# SC.net
KiCad netlist of a schematic drawn in EAGLE
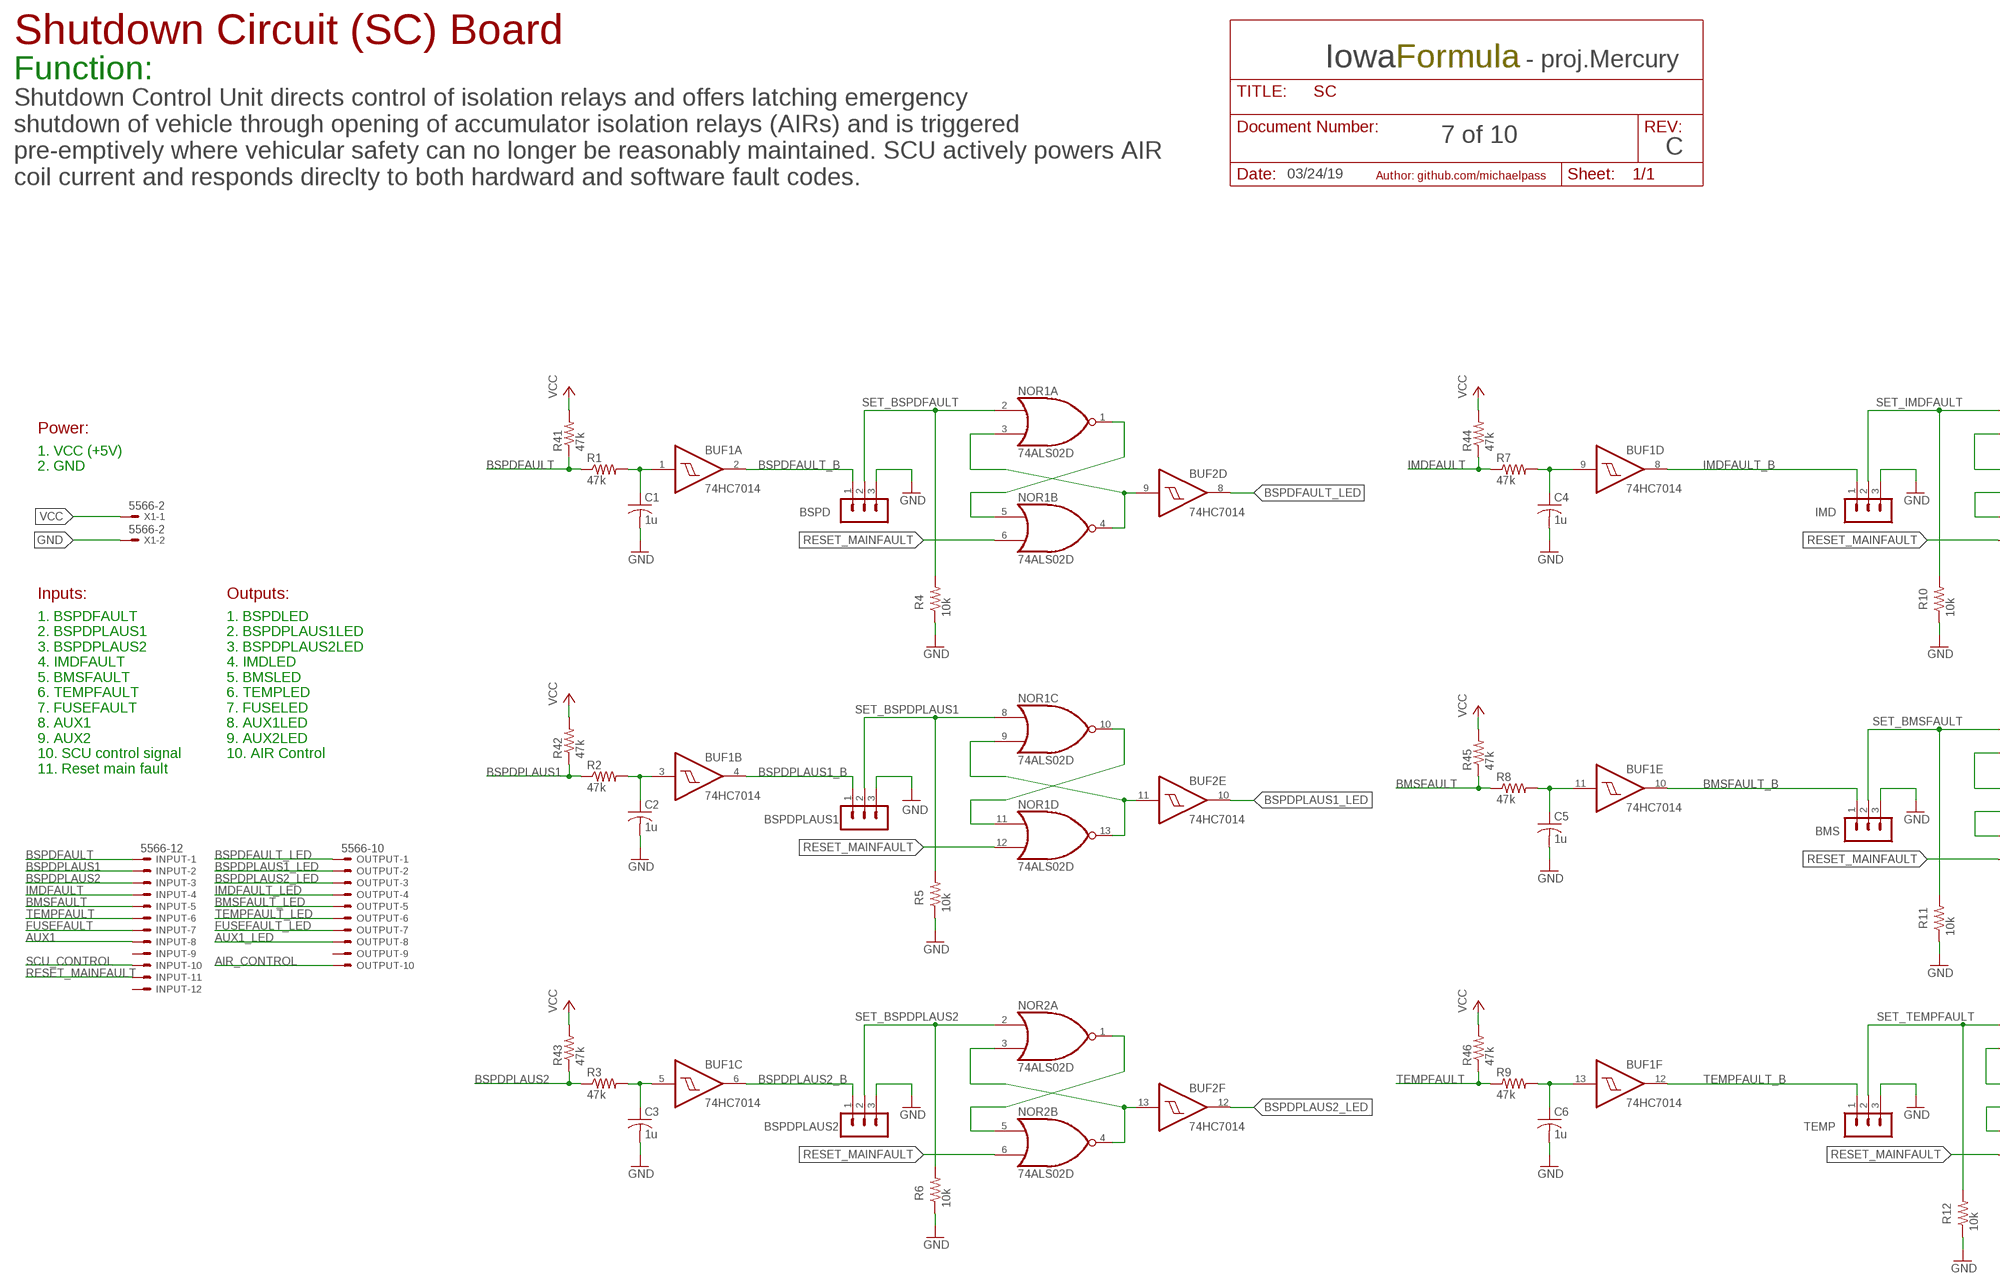
[diagram p0: schematic, sheet 1, part 1 of 3]
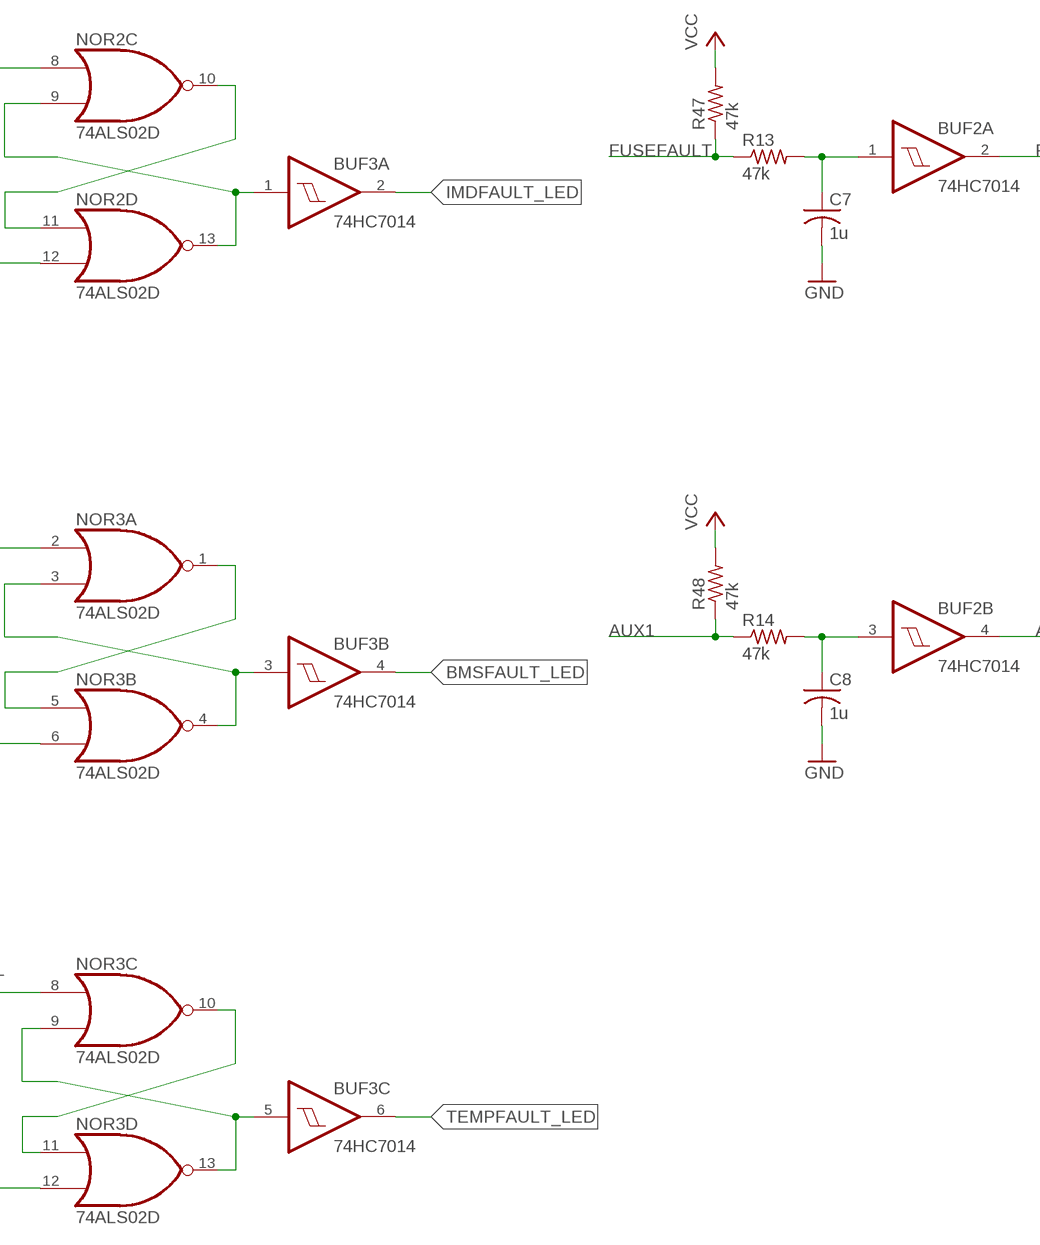
[diagram p1: schematic, sheet 1, part 2 of 3]
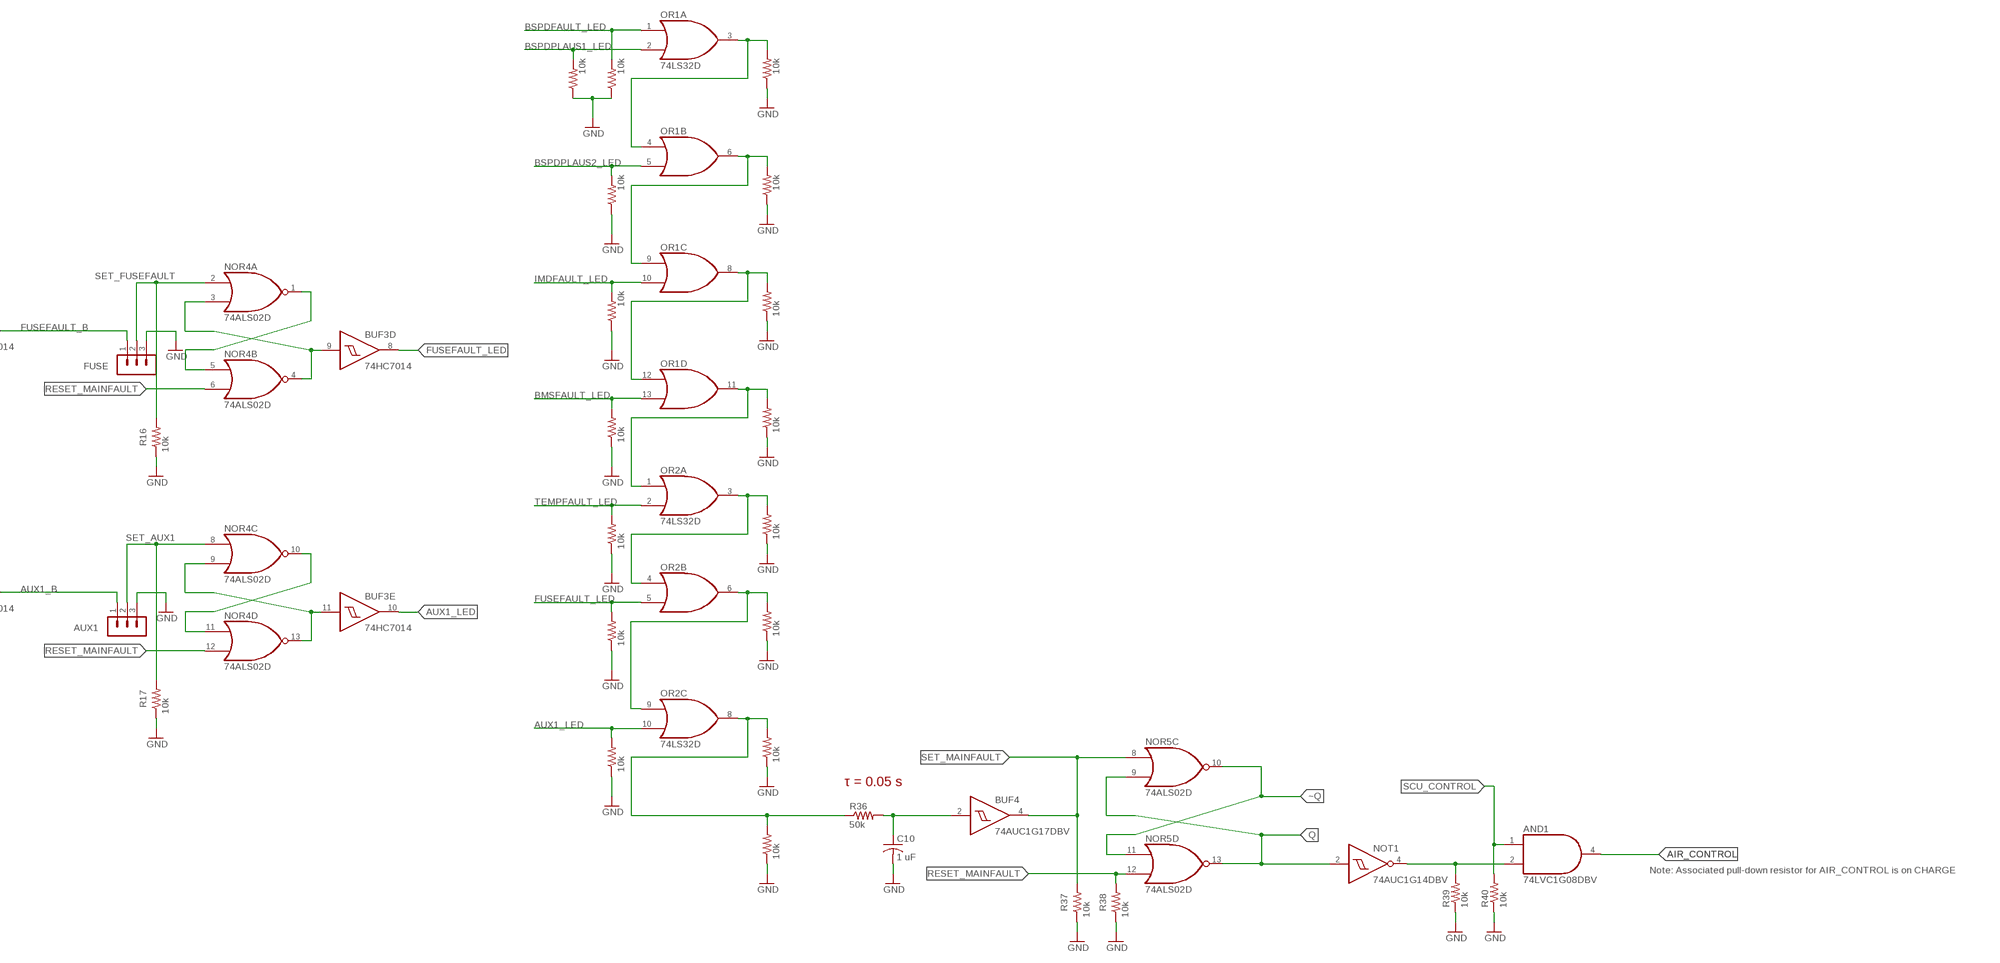
[diagram p2: schematic, sheet 1, part 3 of 3]

(export (version "E")
  (design (tool "Eeschema 10.0.6"))
  (components
    (comp (ref "AND1")
      (value "74LVC1G08DBV")
      (footprint "eagle-import:SOT23-5")
      (libsource (lib "eagle-import") (part "741G08DBVLVC"))
    )
    (comp (ref "AUX1")
      (value "MA03-1")
      (footprint "eagle-import:MA03-1")
      (libsource (lib "eagle-import") (part "MA03-1"))
    )
    (comp (ref "BMS")
      (value "MA03-1")
      (footprint "eagle-import:MA03-1")
      (libsource (lib "eagle-import") (part "MA03-1"))
    )
    (comp (ref "BSPD")
      (value "MA03-1")
      (footprint "eagle-import:MA03-1")
      (libsource (lib "eagle-import") (part "MA03-1"))
    )
    (comp (ref "BSPDPLAUS1")
      (value "MA03-1")
      (footprint "eagle-import:MA03-1")
      (libsource (lib "eagle-import") (part "MA03-1"))
    )
    (comp (ref "BSPDPLAUS2")
      (value "MA03-1")
      (footprint "eagle-import:MA03-1")
      (libsource (lib "eagle-import") (part "MA03-1"))
    )
    (comp (ref "BUF1")
      (value "74HC7014")
      (footprint "eagle-import:SO14")
      (libsource (lib "eagle-import") (part "74HC7014"))
    )
    (comp (ref "BUF2")
      (value "74HC7014")
      (footprint "eagle-import:SO14")
      (libsource (lib "eagle-import") (part "74HC7014"))
    )
    (comp (ref "BUF3")
      (value "74HC7014")
      (footprint "eagle-import:SO14")
      (libsource (lib "eagle-import") (part "74HC7014"))
    )
    (comp (ref "BUF4")
      (value "74AUC1G17DBV")
      (footprint "eagle-import:SOT23-5")
      (libsource (lib "eagle-import") (part "741G17DBVAUC"))
    )
    (comp (ref "C1")
      (value "1u")
      (footprint "eagle-import:C0805")
      (libsource (lib "eagle-import") (part "C-USC0805"))
    )
    (comp (ref "C2")
      (value "1u")
      (footprint "eagle-import:C0805")
      (libsource (lib "eagle-import") (part "C-USC0805"))
    )
    (comp (ref "C3")
      (value "1u")
      (footprint "eagle-import:C0805")
      (libsource (lib "eagle-import") (part "C-USC0805"))
    )
    (comp (ref "C4")
      (value "1u")
      (footprint "eagle-import:C0805")
      (libsource (lib "eagle-import") (part "C-USC0805"))
    )
    (comp (ref "C5")
      (value "1u")
      (footprint "eagle-import:C0805")
      (libsource (lib "eagle-import") (part "C-USC0805"))
    )
    (comp (ref "C6")
      (value "1u")
      (footprint "eagle-import:C0805")
      (libsource (lib "eagle-import") (part "C-USC0805"))
    )
    (comp (ref "C7")
      (value "1u")
      (footprint "eagle-import:C0805")
      (libsource (lib "eagle-import") (part "C-USC0805"))
    )
    (comp (ref "C8")
      (value "1u")
      (footprint "eagle-import:C0805")
      (libsource (lib "eagle-import") (part "C-USC0805"))
    )
    (comp (ref "C10")
      (value "1 uF")
      (footprint "eagle-import:C0805")
      (libsource (lib "eagle-import") (part "C-USC0805"))
    )
    (comp (ref "FUSE")
      (value "MA03-1")
      (footprint "eagle-import:MA03-1")
      (libsource (lib "eagle-import") (part "MA03-1"))
    )
    (comp (ref "IMD")
      (value "MA03-1")
      (footprint "eagle-import:MA03-1")
      (libsource (lib "eagle-import") (part "MA03-1"))
    )
    (comp (ref "INPUT")
      (value "5566-12")
      (footprint "eagle-import:5566-12")
      (fields (field (name "MF") "MOLEX"))
      (libsource (lib "eagle-import") (part "5566-12"))
    )
    (comp (ref "NOR1")
      (value "74ALS02D")
      (footprint "eagle-import:SO14")
      (libsource (lib "eagle-import") (part "7402DALS"))
    )
    (comp (ref "NOR2")
      (value "74ALS02D")
      (footprint "eagle-import:SO14")
      (libsource (lib "eagle-import") (part "7402DALS"))
    )
    (comp (ref "NOR3")
      (value "74ALS02D")
      (footprint "eagle-import:SO14")
      (libsource (lib "eagle-import") (part "7402DALS"))
    )
    (comp (ref "NOR4")
      (value "74ALS02D")
      (footprint "eagle-import:SO14")
      (libsource (lib "eagle-import") (part "7402DALS"))
    )
    (comp (ref "NOR5")
      (value "74ALS02D")
      (footprint "eagle-import:SO14")
      (libsource (lib "eagle-import") (part "7402DALS"))
    )
    (comp (ref "NOT1")
      (value "74AUC1G14DBV")
      (footprint "eagle-import:SOT23-5")
      (libsource (lib "eagle-import") (part "741G14DBVAUC"))
    )
    (comp (ref "OR1")
      (value "74LS32D")
      (footprint "eagle-import:SO14")
      (libsource (lib "eagle-import") (part "7432DLS"))
    )
    (comp (ref "OR2")
      (value "74LS32D")
      (footprint "eagle-import:SO14")
      (libsource (lib "eagle-import") (part "7432DLS"))
    )
    (comp (ref "OUTPUT")
      (value "5566-10")
      (footprint "eagle-import:5566-10")
      (fields (field (name "MF") "MOLEX"))
      (libsource (lib "eagle-import") (part "5566-10"))
    )
    (comp (ref "R1")
      (value "47k")
      (footprint "eagle-import:R0805")
      (libsource (lib "eagle-import") (part "R-US_R0805"))
    )
    (comp (ref "R2")
      (value "47k")
      (footprint "eagle-import:R0805")
      (libsource (lib "eagle-import") (part "R-US_R0805"))
    )
    (comp (ref "R3")
      (value "47k")
      (footprint "eagle-import:R0805")
      (libsource (lib "eagle-import") (part "R-US_R0805"))
    )
    (comp (ref "R4")
      (value "10k")
      (footprint "eagle-import:R0805")
      (libsource (lib "eagle-import") (part "R-US_R0805"))
    )
    (comp (ref "R5")
      (value "10k")
      (footprint "eagle-import:R0805")
      (libsource (lib "eagle-import") (part "R-US_R0805"))
    )
    (comp (ref "R6")
      (value "10k")
      (footprint "eagle-import:R0805")
      (libsource (lib "eagle-import") (part "R-US_R0805"))
    )
    (comp (ref "R7")
      (value "47k")
      (footprint "eagle-import:R0805")
      (libsource (lib "eagle-import") (part "R-US_R0805"))
    )
    (comp (ref "R8")
      (value "47k")
      (footprint "eagle-import:R0805")
      (libsource (lib "eagle-import") (part "R-US_R0805"))
    )
    (comp (ref "R9")
      (value "47k")
      (footprint "eagle-import:R0805")
      (libsource (lib "eagle-import") (part "R-US_R0805"))
    )
    (comp (ref "R10")
      (value "10k")
      (footprint "eagle-import:R0805")
      (libsource (lib "eagle-import") (part "R-US_R0805"))
    )
    (comp (ref "R11")
      (value "10k")
      (footprint "eagle-import:R0805")
      (libsource (lib "eagle-import") (part "R-US_R0805"))
    )
    (comp (ref "R12")
      (value "10k")
      (footprint "eagle-import:R0805")
      (libsource (lib "eagle-import") (part "R-US_R0805"))
    )
    (comp (ref "R13")
      (value "47k")
      (footprint "eagle-import:R0805")
      (libsource (lib "eagle-import") (part "R-US_R0805"))
    )
    (comp (ref "R14")
      (value "47k")
      (footprint "eagle-import:R0805")
      (libsource (lib "eagle-import") (part "R-US_R0805"))
    )
    (comp (ref "R16")
      (value "10k")
      (footprint "eagle-import:R0805")
      (libsource (lib "eagle-import") (part "R-US_R0805"))
    )
    (comp (ref "R17")
      (value "10k")
      (footprint "eagle-import:R0805")
      (libsource (lib "eagle-import") (part "R-US_R0805"))
    )
    (comp (ref "R19")
      (value "10k")
      (footprint "eagle-import:R0805")
      (libsource (lib "eagle-import") (part "R-US_R0805"))
    )
    (comp (ref "R20")
      (value "10k")
      (footprint "eagle-import:R0805")
      (libsource (lib "eagle-import") (part "R-US_R0805"))
    )
    (comp (ref "R21")
      (value "10k")
      (footprint "eagle-import:R0805")
      (libsource (lib "eagle-import") (part "R-US_R0805"))
    )
    (comp (ref "R22")
      (value "10k")
      (footprint "eagle-import:R0805")
      (libsource (lib "eagle-import") (part "R-US_R0805"))
    )
    (comp (ref "R23")
      (value "10k")
      (footprint "eagle-import:R0805")
      (libsource (lib "eagle-import") (part "R-US_R0805"))
    )
    (comp (ref "R24")
      (value "10k")
      (footprint "eagle-import:R0805")
      (libsource (lib "eagle-import") (part "R-US_R0805"))
    )
    (comp (ref "R25")
      (value "10k")
      (footprint "eagle-import:R0805")
      (libsource (lib "eagle-import") (part "R-US_R0805"))
    )
    (comp (ref "R26")
      (value "10k")
      (footprint "eagle-import:R0805")
      (libsource (lib "eagle-import") (part "R-US_R0805"))
    )
    (comp (ref "R28")
      (value "10k")
      (footprint "eagle-import:R0805")
      (libsource (lib "eagle-import") (part "R-US_R0805"))
    )
    (comp (ref "R29")
      (value "10k")
      (footprint "eagle-import:R0805")
      (libsource (lib "eagle-import") (part "R-US_R0805"))
    )
    (comp (ref "R30")
      (value "10k")
      (footprint "eagle-import:R0805")
      (libsource (lib "eagle-import") (part "R-US_R0805"))
    )
    (comp (ref "R31")
      (value "10k")
      (footprint "eagle-import:R0805")
      (libsource (lib "eagle-import") (part "R-US_R0805"))
    )
    (comp (ref "R32")
      (value "10k")
      (footprint "eagle-import:R0805")
      (libsource (lib "eagle-import") (part "R-US_R0805"))
    )
    (comp (ref "R33")
      (value "10k")
      (footprint "eagle-import:R0805")
      (libsource (lib "eagle-import") (part "R-US_R0805"))
    )
    (comp (ref "R34")
      (value "10k")
      (footprint "eagle-import:R0805")
      (libsource (lib "eagle-import") (part "R-US_R0805"))
    )
    (comp (ref "R35")
      (value "10k")
      (footprint "eagle-import:R0805")
      (libsource (lib "eagle-import") (part "R-US_R0805"))
    )
    (comp (ref "R36")
      (value "50k")
      (footprint "eagle-import:R0805")
      (libsource (lib "eagle-import") (part "R-US_R0805"))
    )
    (comp (ref "R37")
      (value "10k")
      (footprint "eagle-import:R0805")
      (libsource (lib "eagle-import") (part "R-US_R0805"))
    )
    (comp (ref "R38")
      (value "10k")
      (footprint "eagle-import:R0805")
      (libsource (lib "eagle-import") (part "R-US_R0805"))
    )
    (comp (ref "R39")
      (value "10k")
      (footprint "eagle-import:R0805")
      (libsource (lib "eagle-import") (part "R-US_R0805"))
    )
    (comp (ref "R40")
      (value "10k")
      (footprint "eagle-import:R0805")
      (libsource (lib "eagle-import") (part "R-US_R0805"))
    )
    (comp (ref "R41")
      (value "47k")
      (footprint "eagle-import:R0805")
      (libsource (lib "eagle-import") (part "R-US_R0805"))
    )
    (comp (ref "R42")
      (value "47k")
      (footprint "eagle-import:R0805")
      (libsource (lib "eagle-import") (part "R-US_R0805"))
    )
    (comp (ref "R43")
      (value "47k")
      (footprint "eagle-import:R0805")
      (libsource (lib "eagle-import") (part "R-US_R0805"))
    )
    (comp (ref "R44")
      (value "47k")
      (footprint "eagle-import:R0805")
      (libsource (lib "eagle-import") (part "R-US_R0805"))
    )
    (comp (ref "R45")
      (value "47k")
      (footprint "eagle-import:R0805")
      (libsource (lib "eagle-import") (part "R-US_R0805"))
    )
    (comp (ref "R46")
      (value "47k")
      (footprint "eagle-import:R0805")
      (libsource (lib "eagle-import") (part "R-US_R0805"))
    )
    (comp (ref "R47")
      (value "47k")
      (footprint "eagle-import:R0805")
      (libsource (lib "eagle-import") (part "R-US_R0805"))
    )
    (comp (ref "R48")
      (value "47k")
      (footprint "eagle-import:R0805")
      (libsource (lib "eagle-import") (part "R-US_R0805"))
    )
    (comp (ref "TEMP")
      (value "MA03-1")
      (footprint "eagle-import:MA03-1")
      (libsource (lib "eagle-import") (part "MA03-1"))
    )
    (comp (ref "X1")
      (value "5566-2")
      (footprint "eagle-import:5566-2")
      (fields (field (name "MF") "MOLEX"))
      (libsource (lib "eagle-import") (part "5566-2"))
    )
  )
  (nets
    (net (code "1") (name "/AUX1") (class "Default")
      (node (ref "INPUT") (pin "8") (pinfunction "S_8") (pintype "passive"))
      (node (ref "R14") (pin "1") (pinfunction "1_1") (pintype "passive"))
      (node (ref "R48") (pin "1") (pinfunction "1_1") (pintype "passive"))
    )
    (net (code "2") (name "/AUX1_B") (class "Default")
      (node (ref "AUX1") (pin "1") (pinfunction "1_1") (pintype "passive"))
      (node (ref "BUF2") (pin "4") (pinfunction "O_4") (pintype "output"))
    )
    (net (code "3") (name "/BMSFAULT") (class "Default")
      (node (ref "INPUT") (pin "5") (pinfunction "S_5") (pintype "passive"))
      (node (ref "R45") (pin "1") (pinfunction "1_1") (pintype "passive"))
      (node (ref "R8") (pin "1") (pinfunction "1_1") (pintype "passive"))
    )
    (net (code "4") (name "/BMSFAULT_B") (class "Default")
      (node (ref "BMS") (pin "1") (pinfunction "1_1") (pintype "passive"))
      (node (ref "BUF1") (pin "10") (pinfunction "O_10") (pintype "output"))
    )
    (net (code "5") (name "/BSPDFAULT") (class "Default")
      (node (ref "INPUT") (pin "1") (pinfunction "S_1") (pintype "passive"))
      (node (ref "R1") (pin "1") (pinfunction "1_1") (pintype "passive"))
      (node (ref "R41") (pin "1") (pinfunction "1_1") (pintype "passive"))
    )
    (net (code "6") (name "/BSPDFAULT_B") (class "Default")
      (node (ref "BSPD") (pin "1") (pinfunction "1_1") (pintype "passive"))
      (node (ref "BUF1") (pin "2") (pinfunction "O_2") (pintype "output"))
    )
    (net (code "7") (name "/BSPDPLAUS1") (class "Default")
      (node (ref "INPUT") (pin "2") (pinfunction "S_2") (pintype "passive"))
      (node (ref "R2") (pin "1") (pinfunction "1_1") (pintype "passive"))
      (node (ref "R42") (pin "1") (pinfunction "1_1") (pintype "passive"))
    )
    (net (code "8") (name "/BSPDPLAUS1_B") (class "Default")
      (node (ref "BSPDPLAUS1") (pin "1") (pinfunction "1_1") (pintype "passive"))
      (node (ref "BUF1") (pin "4") (pinfunction "O_4") (pintype "output"))
    )
    (net (code "9") (name "/BSPDPLAUS2") (class "Default")
      (node (ref "INPUT") (pin "3") (pinfunction "S_3") (pintype "passive"))
      (node (ref "R3") (pin "1") (pinfunction "1_1") (pintype "passive"))
      (node (ref "R43") (pin "1") (pinfunction "1_1") (pintype "passive"))
    )
    (net (code "10") (name "/BSPDPLAUS2_B") (class "Default")
      (node (ref "BSPDPLAUS2") (pin "1") (pinfunction "1_1") (pintype "passive"))
      (node (ref "BUF1") (pin "6") (pinfunction "O_6") (pintype "output"))
    )
    (net (code "11") (name "/FUSEFAULT") (class "Default")
      (node (ref "INPUT") (pin "7") (pinfunction "S_7") (pintype "passive"))
      (node (ref "R13") (pin "1") (pinfunction "1_1") (pintype "passive"))
      (node (ref "R47") (pin "1") (pinfunction "1_1") (pintype "passive"))
    )
    (net (code "12") (name "/FUSEFAULT_B") (class "Default")
      (node (ref "BUF2") (pin "2") (pinfunction "O_2") (pintype "output"))
      (node (ref "FUSE") (pin "1") (pinfunction "1_1") (pintype "passive"))
    )
    (net (code "13") (name "/IMDFAULT") (class "Default")
      (node (ref "INPUT") (pin "4") (pinfunction "S_4") (pintype "passive"))
      (node (ref "R44") (pin "1") (pinfunction "1_1") (pintype "passive"))
      (node (ref "R7") (pin "1") (pinfunction "1_1") (pintype "passive"))
    )
    (net (code "14") (name "/IMDFAULT_B") (class "Default")
      (node (ref "BUF1") (pin "8") (pinfunction "O_8") (pintype "output"))
      (node (ref "IMD") (pin "1") (pinfunction "1_1") (pintype "passive"))
    )
    (net (code "15") (name "/SET_AUX1") (class "Default")
      (node (ref "AUX1") (pin "2") (pinfunction "2_2") (pintype "passive"))
      (node (ref "NOR4") (pin "8") (pinfunction "I0_8") (pintype "input"))
      (node (ref "R17") (pin "2") (pinfunction "2_2") (pintype "passive"))
    )
    (net (code "16") (name "/SET_BMSFAULT") (class "Default")
      (node (ref "BMS") (pin "2") (pinfunction "2_2") (pintype "passive"))
      (node (ref "NOR3") (pin "2") (pinfunction "I0_2") (pintype "input"))
      (node (ref "R11") (pin "2") (pinfunction "2_2") (pintype "passive"))
    )
    (net (code "17") (name "/SET_BSPDFAULT") (class "Default")
      (node (ref "BSPD") (pin "2") (pinfunction "2_2") (pintype "passive"))
      (node (ref "NOR1") (pin "2") (pinfunction "I0_2") (pintype "input"))
      (node (ref "R4") (pin "2") (pinfunction "2_2") (pintype "passive"))
    )
    (net (code "18") (name "/SET_BSPDPLAUS1") (class "Default")
      (node (ref "BSPDPLAUS1") (pin "2") (pinfunction "2_2") (pintype "passive"))
      (node (ref "NOR1") (pin "8") (pinfunction "I0_8") (pintype "input"))
      (node (ref "R5") (pin "2") (pinfunction "2_2") (pintype "passive"))
    )
    (net (code "19") (name "/SET_BSPDPLAUS2") (class "Default")
      (node (ref "BSPDPLAUS2") (pin "2") (pinfunction "2_2") (pintype "passive"))
      (node (ref "NOR2") (pin "2") (pinfunction "I0_2") (pintype "input"))
      (node (ref "R6") (pin "2") (pinfunction "2_2") (pintype "passive"))
    )
    (net (code "20") (name "/SET_FUSEFAULT") (class "Default")
      (node (ref "FUSE") (pin "2") (pinfunction "2_2") (pintype "passive"))
      (node (ref "NOR4") (pin "2") (pinfunction "I0_2") (pintype "input"))
      (node (ref "R16") (pin "2") (pinfunction "2_2") (pintype "passive"))
    )
    (net (code "21") (name "/SET_IMDFAULT") (class "Default")
      (node (ref "IMD") (pin "2") (pinfunction "2_2") (pintype "passive"))
      (node (ref "NOR2") (pin "8") (pinfunction "I0_8") (pintype "input"))
      (node (ref "R10") (pin "2") (pinfunction "2_2") (pintype "passive"))
    )
    (net (code "22") (name "/SET_TEMPFAULT") (class "Default")
      (node (ref "NOR3") (pin "8") (pinfunction "I0_8") (pintype "input"))
      (node (ref "R12") (pin "2") (pinfunction "2_2") (pintype "passive"))
      (node (ref "TEMP") (pin "2") (pinfunction "2_2") (pintype "passive"))
    )
    (net (code "23") (name "/TEMPFAULT") (class "Default")
      (node (ref "INPUT") (pin "6") (pinfunction "S_6") (pintype "passive"))
      (node (ref "R46") (pin "1") (pinfunction "1_1") (pintype "passive"))
      (node (ref "R9") (pin "1") (pinfunction "1_1") (pintype "passive"))
    )
    (net (code "24") (name "/TEMPFAULT_B") (class "Default")
      (node (ref "BUF1") (pin "12") (pinfunction "O_12") (pintype "output"))
      (node (ref "TEMP") (pin "1") (pinfunction "1_1") (pintype "passive"))
    )
    (net (code "25") (name "/~{Q}") (class "Default")
      (node (ref "NOR5") (pin "10") (pinfunction "O_10") (pintype "output"))
      (node (ref "NOR5") (pin "11") (pinfunction "I0_11") (pintype "input"))
    )
    (net (code "26") (name "AIR_CONTROL") (class "Default")
      (node (ref "AND1") (pin "4") (pinfunction "O_4") (pintype "output"))
      (node (ref "OUTPUT") (pin "10") (pinfunction "S_10") (pintype "passive"))
    )
    (net (code "27") (name "AUX1_LED") (class "Default")
      (node (ref "BUF3") (pin "10") (pinfunction "O_10") (pintype "output"))
      (node (ref "OR2") (pin "10") (pinfunction "I1_10") (pintype "input"))
      (node (ref "OUTPUT") (pin "8") (pinfunction "S_8") (pintype "passive"))
      (node (ref "R26") (pin "2") (pinfunction "2_2") (pintype "passive"))
    )
    (net (code "28") (name "BMSFAULT_LED") (class "Default")
      (node (ref "BUF3") (pin "4") (pinfunction "O_4") (pintype "output"))
      (node (ref "OR1") (pin "13") (pinfunction "I1_13") (pintype "input"))
      (node (ref "OUTPUT") (pin "5") (pinfunction "S_5") (pintype "passive"))
      (node (ref "R23") (pin "2") (pinfunction "2_2") (pintype "passive"))
    )
    (net (code "29") (name "BSPDFAULT_LED") (class "Default")
      (node (ref "BUF2") (pin "8") (pinfunction "O_8") (pintype "output"))
      (node (ref "OR1") (pin "1") (pinfunction "I0_1") (pintype "input"))
      (node (ref "OUTPUT") (pin "1") (pinfunction "S_1") (pintype "passive"))
      (node (ref "R20") (pin "2") (pinfunction "2_2") (pintype "passive"))
    )
    (net (code "30") (name "BSPDPLAUS1_LED") (class "Default")
      (node (ref "BUF2") (pin "10") (pinfunction "O_10") (pintype "output"))
      (node (ref "OR1") (pin "2") (pinfunction "I1_2") (pintype "input"))
      (node (ref "OUTPUT") (pin "2") (pinfunction "S_2") (pintype "passive"))
      (node (ref "R19") (pin "2") (pinfunction "2_2") (pintype "passive"))
    )
    (net (code "31") (name "BSPDPLAUS2_LED") (class "Default")
      (node (ref "BUF2") (pin "12") (pinfunction "O_12") (pintype "output"))
      (node (ref "OR1") (pin "5") (pinfunction "I1_5") (pintype "input"))
      (node (ref "OUTPUT") (pin "3") (pinfunction "S_3") (pintype "passive"))
      (node (ref "R21") (pin "2") (pinfunction "2_2") (pintype "passive"))
    )
    (net (code "32") (name "FUSEFAULT_LED") (class "Default")
      (node (ref "BUF3") (pin "8") (pinfunction "O_8") (pintype "output"))
      (node (ref "OR2") (pin "5") (pinfunction "I1_5") (pintype "input"))
      (node (ref "OUTPUT") (pin "7") (pinfunction "S_7") (pintype "passive"))
      (node (ref "R25") (pin "2") (pinfunction "2_2") (pintype "passive"))
    )
    (net (code "33") (name "GND") (class "Default")
      (node (ref "AUX1") (pin "3") (pinfunction "3_3") (pintype "passive"))
      (node (ref "BMS") (pin "3") (pinfunction "3_3") (pintype "passive"))
      (node (ref "BSPD") (pin "3") (pinfunction "3_3") (pintype "passive"))
      (node (ref "BSPDPLAUS1") (pin "3") (pinfunction "3_3") (pintype "passive"))
      (node (ref "BSPDPLAUS2") (pin "3") (pinfunction "3_3") (pintype "passive"))
      (node (ref "C1") (pin "2") (pinfunction "2_2") (pintype "passive"))
      (node (ref "C10") (pin "2") (pinfunction "2_2") (pintype "passive"))
      (node (ref "C2") (pin "2") (pinfunction "2_2") (pintype "passive"))
      (node (ref "C3") (pin "2") (pinfunction "2_2") (pintype "passive"))
      (node (ref "C4") (pin "2") (pinfunction "2_2") (pintype "passive"))
      (node (ref "C5") (pin "2") (pinfunction "2_2") (pintype "passive"))
      (node (ref "C6") (pin "2") (pinfunction "2_2") (pintype "passive"))
      (node (ref "C7") (pin "2") (pinfunction "2_2") (pintype "passive"))
      (node (ref "C8") (pin "2") (pinfunction "2_2") (pintype "passive"))
      (node (ref "FUSE") (pin "3") (pinfunction "3_3") (pintype "passive"))
      (node (ref "IMD") (pin "3") (pinfunction "3_3") (pintype "passive"))
      (node (ref "R10") (pin "1") (pinfunction "1_1") (pintype "passive"))
      (node (ref "R11") (pin "1") (pinfunction "1_1") (pintype "passive"))
      (node (ref "R12") (pin "1") (pinfunction "1_1") (pintype "passive"))
      (node (ref "R16") (pin "1") (pinfunction "1_1") (pintype "passive"))
      (node (ref "R17") (pin "1") (pinfunction "1_1") (pintype "passive"))
      (node (ref "R19") (pin "1") (pinfunction "1_1") (pintype "passive"))
      (node (ref "R20") (pin "1") (pinfunction "1_1") (pintype "passive"))
      (node (ref "R21") (pin "1") (pinfunction "1_1") (pintype "passive"))
      (node (ref "R22") (pin "1") (pinfunction "1_1") (pintype "passive"))
      (node (ref "R23") (pin "1") (pinfunction "1_1") (pintype "passive"))
      (node (ref "R24") (pin "1") (pinfunction "1_1") (pintype "passive"))
      (node (ref "R25") (pin "1") (pinfunction "1_1") (pintype "passive"))
      (node (ref "R26") (pin "1") (pinfunction "1_1") (pintype "passive"))
      (node (ref "R28") (pin "1") (pinfunction "1_1") (pintype "passive"))
      (node (ref "R29") (pin "1") (pinfunction "1_1") (pintype "passive"))
      (node (ref "R30") (pin "1") (pinfunction "1_1") (pintype "passive"))
      (node (ref "R31") (pin "1") (pinfunction "1_1") (pintype "passive"))
      (node (ref "R32") (pin "1") (pinfunction "1_1") (pintype "passive"))
      (node (ref "R33") (pin "1") (pinfunction "1_1") (pintype "passive"))
      (node (ref "R34") (pin "1") (pinfunction "1_1") (pintype "passive"))
      (node (ref "R35") (pin "1") (pinfunction "1_1") (pintype "passive"))
      (node (ref "R37") (pin "1") (pinfunction "1_1") (pintype "passive"))
      (node (ref "R38") (pin "1") (pinfunction "1_1") (pintype "passive"))
      (node (ref "R39") (pin "1") (pinfunction "1_1") (pintype "passive"))
      (node (ref "R4") (pin "1") (pinfunction "1_1") (pintype "passive"))
      (node (ref "R40") (pin "1") (pinfunction "1_1") (pintype "passive"))
      (node (ref "R5") (pin "1") (pinfunction "1_1") (pintype "passive"))
      (node (ref "R6") (pin "1") (pinfunction "1_1") (pintype "passive"))
      (node (ref "TEMP") (pin "3") (pinfunction "3_3") (pintype "passive"))
      (node (ref "X1") (pin "2") (pinfunction "S_2") (pintype "passive"))
    )
    (net (code "34") (name "IMDFAULT_LED") (class "Default")
      (node (ref "BUF3") (pin "2") (pinfunction "O_2") (pintype "output"))
      (node (ref "OR1") (pin "10") (pinfunction "I1_10") (pintype "input"))
      (node (ref "OUTPUT") (pin "4") (pinfunction "S_4") (pintype "passive"))
      (node (ref "R22") (pin "2") (pinfunction "2_2") (pintype "passive"))
    )
    (net (code "35") (name "Net-(AND1A-I1)") (class "Default")
      (node (ref "AND1") (pin "2") (pinfunction "I1_2") (pintype "input"))
      (node (ref "NOT1") (pin "4") (pinfunction "O_4") (pintype "output"))
      (node (ref "R39") (pin "2") (pinfunction "2_2") (pintype "passive"))
    )
    (net (code "36") (name "Net-(BUF1A-I)") (class "Default")
      (node (ref "BUF1") (pin "1") (pinfunction "I_1") (pintype "input"))
      (node (ref "C1") (pin "1") (pinfunction "1_1") (pintype "passive"))
      (node (ref "R1") (pin "2") (pinfunction "2_2") (pintype "passive"))
    )
    (net (code "37") (name "Net-(BUF1B-I)") (class "Default")
      (node (ref "BUF1") (pin "3") (pinfunction "I_3") (pintype "input"))
      (node (ref "C2") (pin "1") (pinfunction "1_1") (pintype "passive"))
      (node (ref "R2") (pin "2") (pinfunction "2_2") (pintype "passive"))
    )
    (net (code "38") (name "Net-(BUF1C-I)") (class "Default")
      (node (ref "BUF1") (pin "5") (pinfunction "I_5") (pintype "input"))
      (node (ref "C3") (pin "1") (pinfunction "1_1") (pintype "passive"))
      (node (ref "R3") (pin "2") (pinfunction "2_2") (pintype "passive"))
    )
    (net (code "39") (name "Net-(BUF1D-I)") (class "Default")
      (node (ref "BUF1") (pin "9") (pinfunction "I_9") (pintype "input"))
      (node (ref "C4") (pin "1") (pinfunction "1_1") (pintype "passive"))
      (node (ref "R7") (pin "2") (pinfunction "2_2") (pintype "passive"))
    )
    (net (code "40") (name "Net-(BUF1E-I)") (class "Default")
      (node (ref "BUF1") (pin "11") (pinfunction "I_11") (pintype "input"))
      (node (ref "C5") (pin "1") (pinfunction "1_1") (pintype "passive"))
      (node (ref "R8") (pin "2") (pinfunction "2_2") (pintype "passive"))
    )
    (net (code "41") (name "Net-(BUF1F-I)") (class "Default")
      (node (ref "BUF1") (pin "13") (pinfunction "I_13") (pintype "input"))
      (node (ref "C6") (pin "1") (pinfunction "1_1") (pintype "passive"))
      (node (ref "R9") (pin "2") (pinfunction "2_2") (pintype "passive"))
    )
    (net (code "42") (name "Net-(BUF2A-I)") (class "Default")
      (node (ref "BUF2") (pin "1") (pinfunction "I_1") (pintype "input"))
      (node (ref "C7") (pin "1") (pinfunction "1_1") (pintype "passive"))
      (node (ref "R13") (pin "2") (pinfunction "2_2") (pintype "passive"))
    )
    (net (code "43") (name "Net-(BUF2B-I)") (class "Default")
      (node (ref "BUF2") (pin "3") (pinfunction "I_3") (pintype "input"))
      (node (ref "C8") (pin "1") (pinfunction "1_1") (pintype "passive"))
      (node (ref "R14") (pin "2") (pinfunction "2_2") (pintype "passive"))
    )
    (net (code "44") (name "Net-(BUF2D-I)") (class "Default")
      (node (ref "BUF2") (pin "9") (pinfunction "I_9") (pintype "input"))
      (node (ref "NOR1") (pin "3") (pinfunction "I1_3") (pintype "input"))
      (node (ref "NOR1") (pin "4") (pinfunction "O_4") (pintype "output"))
    )
    (net (code "45") (name "Net-(BUF2E-I)") (class "Default")
      (node (ref "BUF2") (pin "11") (pinfunction "I_11") (pintype "input"))
      (node (ref "NOR1") (pin "13") (pinfunction "O_13") (pintype "output"))
      (node (ref "NOR1") (pin "9") (pinfunction "I1_9") (pintype "input"))
    )
    (net (code "46") (name "Net-(BUF2F-I)") (class "Default")
      (node (ref "BUF2") (pin "13") (pinfunction "I_13") (pintype "input"))
      (node (ref "NOR2") (pin "3") (pinfunction "I1_3") (pintype "input"))
      (node (ref "NOR2") (pin "4") (pinfunction "O_4") (pintype "output"))
    )
    (net (code "47") (name "Net-(BUF3A-I)") (class "Default")
      (node (ref "BUF3") (pin "1") (pinfunction "I_1") (pintype "input"))
      (node (ref "NOR2") (pin "13") (pinfunction "O_13") (pintype "output"))
      (node (ref "NOR2") (pin "9") (pinfunction "I1_9") (pintype "input"))
    )
    (net (code "48") (name "Net-(BUF3B-I)") (class "Default")
      (node (ref "BUF3") (pin "3") (pinfunction "I_3") (pintype "input"))
      (node (ref "NOR3") (pin "3") (pinfunction "I1_3") (pintype "input"))
      (node (ref "NOR3") (pin "4") (pinfunction "O_4") (pintype "output"))
    )
    (net (code "49") (name "Net-(BUF3C-I)") (class "Default")
      (node (ref "BUF3") (pin "5") (pinfunction "I_5") (pintype "input"))
      (node (ref "NOR3") (pin "13") (pinfunction "O_13") (pintype "output"))
      (node (ref "NOR3") (pin "9") (pinfunction "I1_9") (pintype "input"))
    )
    (net (code "50") (name "Net-(BUF3D-I)") (class "Default")
      (node (ref "BUF3") (pin "9") (pinfunction "I_9") (pintype "input"))
      (node (ref "NOR4") (pin "3") (pinfunction "I1_3") (pintype "input"))
      (node (ref "NOR4") (pin "4") (pinfunction "O_4") (pintype "output"))
    )
    (net (code "51") (name "Net-(BUF3E-I)") (class "Default")
      (node (ref "BUF3") (pin "11") (pinfunction "I_11") (pintype "input"))
      (node (ref "NOR4") (pin "13") (pinfunction "O_13") (pintype "output"))
      (node (ref "NOR4") (pin "9") (pinfunction "I1_9") (pintype "input"))
    )
    (net (code "52") (name "Net-(BUF4A-I)") (class "Default")
      (node (ref "BUF4") (pin "2") (pinfunction "I_2") (pintype "input"))
      (node (ref "C10") (pin "1") (pinfunction "1_1") (pintype "passive"))
      (node (ref "R36") (pin "2") (pinfunction "2_2") (pintype "passive"))
    )
    (net (code "53") (name "Net-(NOR1A-O)") (class "Default")
      (node (ref "NOR1") (pin "1") (pinfunction "O_1") (pintype "output"))
      (node (ref "NOR1") (pin "5") (pinfunction "I0_5") (pintype "input"))
    )
    (net (code "54") (name "Net-(NOR1C-O)") (class "Default")
      (node (ref "NOR1") (pin "10") (pinfunction "O_10") (pintype "output"))
      (node (ref "NOR1") (pin "11") (pinfunction "I0_11") (pintype "input"))
    )
    (net (code "55") (name "Net-(NOR2A-O)") (class "Default")
      (node (ref "NOR2") (pin "1") (pinfunction "O_1") (pintype "output"))
      (node (ref "NOR2") (pin "5") (pinfunction "I0_5") (pintype "input"))
    )
    (net (code "56") (name "Net-(NOR2C-O)") (class "Default")
      (node (ref "NOR2") (pin "10") (pinfunction "O_10") (pintype "output"))
      (node (ref "NOR2") (pin "11") (pinfunction "I0_11") (pintype "input"))
    )
    (net (code "57") (name "Net-(NOR3A-O)") (class "Default")
      (node (ref "NOR3") (pin "1") (pinfunction "O_1") (pintype "output"))
      (node (ref "NOR3") (pin "5") (pinfunction "I0_5") (pintype "input"))
    )
    (net (code "58") (name "Net-(NOR3C-O)") (class "Default")
      (node (ref "NOR3") (pin "10") (pinfunction "O_10") (pintype "output"))
      (node (ref "NOR3") (pin "11") (pinfunction "I0_11") (pintype "input"))
    )
    (net (code "59") (name "Net-(NOR4A-O)") (class "Default")
      (node (ref "NOR4") (pin "1") (pinfunction "O_1") (pintype "output"))
      (node (ref "NOR4") (pin "5") (pinfunction "I0_5") (pintype "input"))
    )
    (net (code "60") (name "Net-(NOR4C-O)") (class "Default")
      (node (ref "NOR4") (pin "10") (pinfunction "O_10") (pintype "output"))
      (node (ref "NOR4") (pin "11") (pinfunction "I0_11") (pintype "input"))
    )
    (net (code "61") (name "Net-(OR1A-O)") (class "Default")
      (node (ref "OR1") (pin "3") (pinfunction "O_3") (pintype "output"))
      (node (ref "OR1") (pin "4") (pinfunction "I0_4") (pintype "input"))
      (node (ref "R28") (pin "2") (pinfunction "2_2") (pintype "passive"))
    )
    (net (code "62") (name "Net-(OR1B-O)") (class "Default")
      (node (ref "OR1") (pin "6") (pinfunction "O_6") (pintype "output"))
      (node (ref "OR1") (pin "9") (pinfunction "I0_9") (pintype "input"))
      (node (ref "R29") (pin "2") (pinfunction "2_2") (pintype "passive"))
    )
    (net (code "63") (name "Net-(OR1C-O)") (class "Default")
      (node (ref "OR1") (pin "12") (pinfunction "I0_12") (pintype "input"))
      (node (ref "OR1") (pin "8") (pinfunction "O_8") (pintype "output"))
      (node (ref "R30") (pin "2") (pinfunction "2_2") (pintype "passive"))
    )
    (net (code "64") (name "Net-(OR1D-O)") (class "Default")
      (node (ref "OR1") (pin "11") (pinfunction "O_11") (pintype "output"))
      (node (ref "OR2") (pin "1") (pinfunction "I0_1") (pintype "input"))
      (node (ref "R31") (pin "2") (pinfunction "2_2") (pintype "passive"))
    )
    (net (code "65") (name "Net-(OR2A-O)") (class "Default")
      (node (ref "OR2") (pin "3") (pinfunction "O_3") (pintype "output"))
      (node (ref "OR2") (pin "4") (pinfunction "I0_4") (pintype "input"))
      (node (ref "R32") (pin "2") (pinfunction "2_2") (pintype "passive"))
    )
    (net (code "66") (name "Net-(OR2B-O)") (class "Default")
      (node (ref "OR2") (pin "6") (pinfunction "O_6") (pintype "output"))
      (node (ref "OR2") (pin "9") (pinfunction "I0_9") (pintype "input"))
      (node (ref "R33") (pin "2") (pinfunction "2_2") (pintype "passive"))
    )
    (net (code "67") (name "Net-(OR2C-O)") (class "Default")
      (node (ref "OR2") (pin "8") (pinfunction "O_8") (pintype "output"))
      (node (ref "R34") (pin "2") (pinfunction "2_2") (pintype "passive"))
      (node (ref "R35") (pin "2") (pinfunction "2_2") (pintype "passive"))
      (node (ref "R36") (pin "1") (pinfunction "1_1") (pintype "passive"))
    )
    (net (code "68") (name "Q") (class "Default")
      (node (ref "NOR5") (pin "13") (pinfunction "O_13") (pintype "output"))
      (node (ref "NOR5") (pin "9") (pinfunction "I1_9") (pintype "input"))
      (node (ref "NOT1") (pin "2") (pinfunction "I_2") (pintype "input"))
    )
    (net (code "69") (name "RESET_MAINFAULT") (class "Default")
      (node (ref "INPUT") (pin "11") (pinfunction "S_11") (pintype "passive"))
      (node (ref "NOR1") (pin "12") (pinfunction "I1_12") (pintype "input"))
      (node (ref "NOR1") (pin "6") (pinfunction "I1_6") (pintype "input"))
      (node (ref "NOR2") (pin "12") (pinfunction "I1_12") (pintype "input"))
      (node (ref "NOR2") (pin "6") (pinfunction "I1_6") (pintype "input"))
      (node (ref "NOR3") (pin "12") (pinfunction "I1_12") (pintype "input"))
      (node (ref "NOR3") (pin "6") (pinfunction "I1_6") (pintype "input"))
      (node (ref "NOR4") (pin "12") (pinfunction "I1_12") (pintype "input"))
      (node (ref "NOR4") (pin "6") (pinfunction "I1_6") (pintype "input"))
      (node (ref "NOR5") (pin "12") (pinfunction "I1_12") (pintype "input"))
      (node (ref "R38") (pin "2") (pinfunction "2_2") (pintype "passive"))
    )
    (net (code "70") (name "SCU_CONTROL") (class "Default")
      (node (ref "AND1") (pin "1") (pinfunction "I0_1") (pintype "input"))
      (node (ref "INPUT") (pin "10") (pinfunction "S_10") (pintype "passive"))
      (node (ref "R40") (pin "2") (pinfunction "2_2") (pintype "passive"))
    )
    (net (code "71") (name "SET_MAINFAULT") (class "Default")
      (node (ref "BUF4") (pin "4") (pinfunction "O_4") (pintype "output"))
      (node (ref "NOR5") (pin "8") (pinfunction "I0_8") (pintype "input"))
      (node (ref "R37") (pin "2") (pinfunction "2_2") (pintype "passive"))
    )
    (net (code "72") (name "TEMPFAULT_LED") (class "Default")
      (node (ref "BUF3") (pin "6") (pinfunction "O_6") (pintype "output"))
      (node (ref "OR2") (pin "2") (pinfunction "I1_2") (pintype "input"))
      (node (ref "OUTPUT") (pin "6") (pinfunction "S_6") (pintype "passive"))
      (node (ref "R24") (pin "2") (pinfunction "2_2") (pintype "passive"))
    )
    (net (code "73") (name "VCC") (class "Default")
      (node (ref "R41") (pin "2") (pinfunction "2_2") (pintype "passive"))
      (node (ref "R42") (pin "2") (pinfunction "2_2") (pintype "passive"))
      (node (ref "R43") (pin "2") (pinfunction "2_2") (pintype "passive"))
      (node (ref "R44") (pin "2") (pinfunction "2_2") (pintype "passive"))
      (node (ref "R45") (pin "2") (pinfunction "2_2") (pintype "passive"))
      (node (ref "R46") (pin "2") (pinfunction "2_2") (pintype "passive"))
      (node (ref "R47") (pin "2") (pinfunction "2_2") (pintype "passive"))
      (node (ref "R48") (pin "2") (pinfunction "2_2") (pintype "passive"))
      (node (ref "X1") (pin "1") (pinfunction "S_1") (pintype "passive"))
    )
    (net (code "74") (name "unconnected-(INPUTD-S-Pad12)") (class "Default")
      (node (ref "INPUT") (pin "12") (pinfunction "S_12") (pintype "passive"))
    )
    (net (code "75") (name "unconnected-(INPUTL-S-Pad9)") (class "Default")
      (node (ref "INPUT") (pin "9") (pinfunction "S_9") (pintype "passive"))
    )
    (net (code "76") (name "unconnected-(OUTPUTJ-S-Pad9)") (class "Default")
      (node (ref "OUTPUT") (pin "9") (pinfunction "S_9") (pintype "passive"))
    )
  )
)
